# Measure.net
KiCad netlist of a schematic drawn in Altium Designer
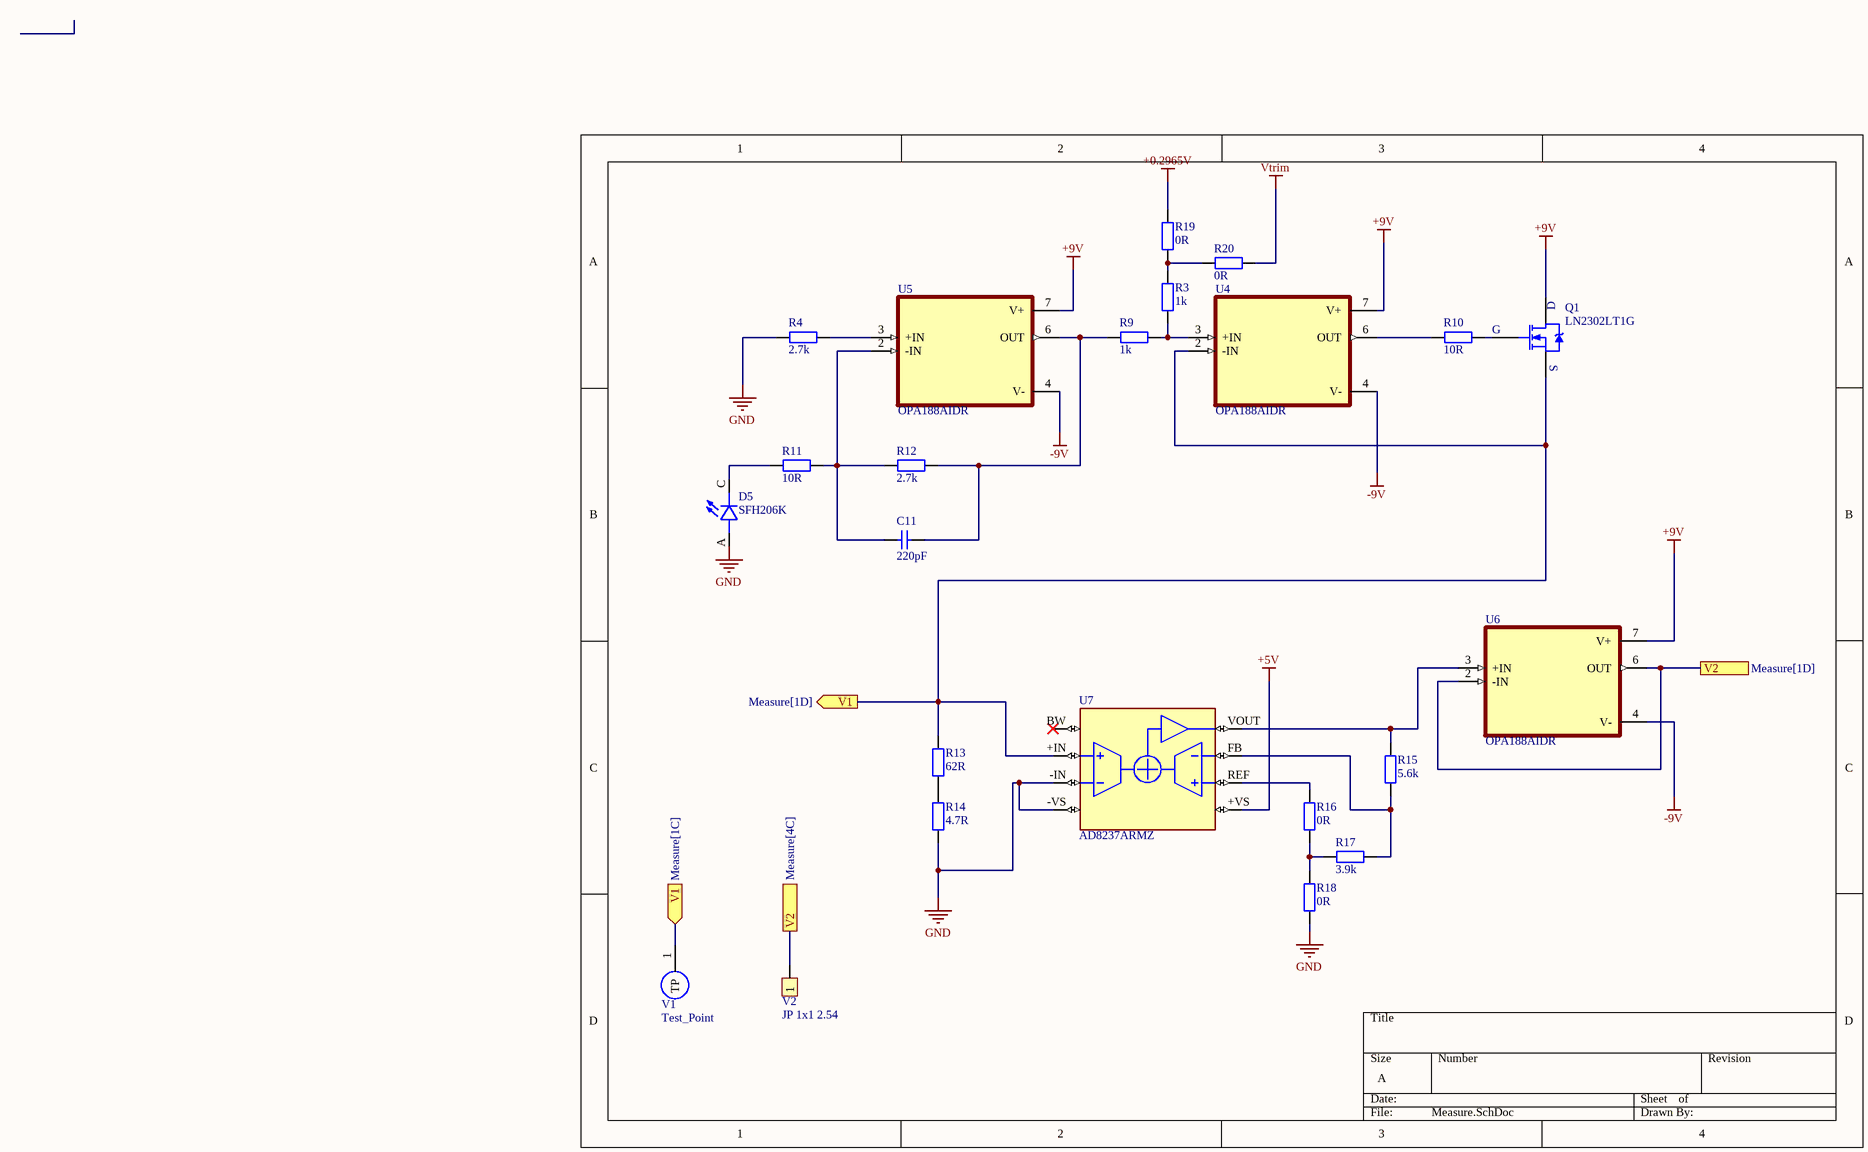
[diagram p0: Measure.SchDoc]

(export (version "E")
  (design (tool "Eeschema 10.0.6"))
  (components
    (comp (ref "C11")
      (value "220pF")
      (footprint "Tu 0603")
      (description "Dán")
      (libsource (lib "Tu dien") (part "Tu 0603 220pF 50V 10%"))
    )
    (comp (ref "D5")
      (value "SFH206K")
      (footprint "SFH206K")
      (description "photodiode, 850nm")
      (fields (field (name "MP") "L08R5000Q1") (field (name "MF") "LED Technology"))
      (libsource (lib "SFH206K") (part "SFH206K"))
    )
    (comp (ref "Q1")
      (value "LN2302LT1G")
      (footprint "SOT95P240X120-3N")
      (description "SOT-23-3, MOSFET kênh N, 20V, 2.3A")
      (libsource (lib "TranFet") (part "MOSFET"))
    )
    (comp (ref "R3")
      (value "1k")
      (footprint "tro smd 0603")
      (description "Dán")
      (libsource (lib "Dien Tro") (part "Tro 0603 1% 1k"))
    )
    (comp (ref "R4")
      (value "2.7k")
      (footprint "TRO SMD 0603")
      (description "dán")
      (libsource (lib "Dien Tro") (part "tro 0603 5% 2.7k"))
    )
    (comp (ref "R9")
      (value "1k")
      (footprint "tro smd 0603")
      (description "Dán")
      (libsource (lib "Dien Tro") (part "Tro 0603 1% 1k"))
    )
    (comp (ref "R10")
      (value "10R")
      (footprint "Tro smd 0603")
      (description "Dán")
      (libsource (lib "Dien Tro") (part "Tro 0603 5% 10R"))
    )
    (comp (ref "R11")
      (value "10R")
      (footprint "Tro smd 0603")
      (description "Dán")
      (libsource (lib "Dien Tro") (part "Tro 0603 5% 10R"))
    )
    (comp (ref "R12")
      (value "2.7k")
      (footprint "TRO SMD 0603")
      (description "dán")
      (libsource (lib "Dien Tro") (part "tro 0603 5% 2.7k"))
    )
    (comp (ref "R13")
      (value "62R")
      (footprint "TRO SMD 0603")
      (description "Dán")
      (libsource (lib "Dien Tro") (part "Tro 0603 1% 62R"))
    )
    (comp (ref "R14")
      (value "4.7R")
      (footprint "TRO SMD 0603")
      (description "Dán")
      (libsource (lib "Dien Tro") (part "Tro 0603 1% 4.7R"))
    )
    (comp (ref "R15")
      (value "5.6k")
      (footprint "TRO SMD 0603")
      (description "Dán")
      (libsource (lib "Dien Tro") (part "Tro 0603 1% 5.6k"))
    )
    (comp (ref "R16")
      (value "0R")
      (footprint "tro smd 0603")
      (description "Dán")
      (libsource (lib "Dien Tro") (part "Tro 0603 1% 0R"))
    )
    (comp (ref "R17")
      (value "3.9k")
      (footprint "TRO SMD 0603")
      (description "Dán")
      (libsource (lib "Dien Tro") (part "Tro 0805 1% 3.9k"))
    )
    (comp (ref "R18")
      (value "0R")
      (footprint "tro smd 0603")
      (description "Dán")
      (libsource (lib "Dien Tro") (part "Tro 0603 1% 0R"))
    )
    (comp (ref "R19")
      (value "0R")
      (footprint "tro smd 0603")
      (description "Dán")
      (libsource (lib "Dien Tro") (part "Tro 0603 1% 0R"))
    )
    (comp (ref "R20")
      (value "0R")
      (footprint "tro smd 0603")
      (description "Dán")
      (libsource (lib "Dien Tro") (part "Tro 0603 1% 0R"))
    )
    (comp (ref "U4")
      (value "OPA188AIDR")
      (footprint "SOIC127P599X175-8N")
      (description "Precision, Low-Noise, Rail-to-Rail Output, 36V Zero-Drift Operational Amplifier 8-SOIC -40 to 125")
      (fields (field (name "MF") "Texas Instruments") (field (name "DIGI-KEY_PART_NUMBER") "296-41346-1-ND"))
      (libsource (lib "OPA188AIDR") (part "OPA188AIDR"))
    )
    (comp (ref "U5")
      (value "OPA188AIDR")
      (footprint "SOIC127P599X175-8N")
      (description "Precision, Low-Noise, Rail-to-Rail Output, 36V Zero-Drift Operational Amplifier 8-SOIC -40 to 125")
      (fields (field (name "MF") "Texas Instruments") (field (name "DIGI-KEY_PART_NUMBER") "296-41346-1-ND"))
      (libsource (lib "OPA188AIDR") (part "OPA188AIDR"))
    )
    (comp (ref "U6")
      (value "OPA188AIDR")
      (footprint "SOIC127P599X175-8N")
      (description "Precision, Low-Noise, Rail-to-Rail Output, 36V Zero-Drift Operational Amplifier 8-SOIC -40 to 125")
      (fields (field (name "MF") "Texas Instruments") (field (name "DIGI-KEY_PART_NUMBER") "296-41346-1-ND"))
      (libsource (lib "OPA188AIDR") (part "OPA188AIDR"))
    )
    (comp (ref "U7")
      (value "AD8237ARMZ")
      (footprint "AD8237ARMZ")
      (description "Micropower, Zero Drift, True Rail-to-Rail Instrumentation Amplifier")
      (fields (field (name "MF") "Analog Devices"))
      (libsource (lib "AD8237ARMZ") (part "AD8237ARMZ"))
    )
    (comp (ref "V1")
      (value "Test_Point")
      (footprint "TP_2MM")
      (description "Test point, 2mm radius")
      (libsource (lib "SMIOT_Lib_Schematic") (part "Test_Point"))
    )
    (comp (ref "V2")
      (value "JP 1x1 2.54")
      (footprint "JP 1x1 DT")
      (description "Cắm")
      (libsource (lib "Jump") (part "JP 1x1 2.54 Duc Cong"))
    )
  )
  (nets
    (net (code "1") (name "+0.2965V") (class "Default")
      (node (ref "R19") (pin "2") (pinfunction "2_2") (pintype "passive"))
    )
    (net (code "2") (name "+5V") (class "Default")
      (node (ref "U7") (pin "+VS") (pinfunction "+VS_+VS") (pintype "bidirectional"))
    )
    (net (code "3") (name "+9V") (class "Default")
      (node (ref "Q1") (pin "3") (pinfunction "D_3") (pintype "passive"))
      (node (ref "U4") (pin "7") (pinfunction "V+_7") (pintype "power_in"))
      (node (ref "U5") (pin "7") (pinfunction "V+_7") (pintype "power_in"))
      (node (ref "U6") (pin "7") (pinfunction "V+_7") (pintype "power_in"))
    )
    (net (code "4") (name "-9V") (class "Default")
      (node (ref "U4") (pin "4") (pinfunction "V-_4") (pintype "power_in"))
      (node (ref "U5") (pin "4") (pinfunction "V-_4") (pintype "power_in"))
      (node (ref "U6") (pin "4") (pinfunction "V-_4") (pintype "power_in"))
    )
    (net (code "5") (name "/V1") (class "Default")
      (node (ref "Q1") (pin "2") (pinfunction "S_2") (pintype "passive"))
      (node (ref "R13") (pin "2") (pinfunction "2_2") (pintype "passive"))
      (node (ref "U4") (pin "2") (pinfunction "-IN_2") (pintype "input"))
      (node (ref "U7") (pin "+IN") (pinfunction "+IN_+IN") (pintype "bidirectional"))
      (node (ref "V1") (pin "1") (pinfunction "TP_1") (pintype "passive"))
    )
    (net (code "6") (name "/V2") (class "Default")
      (node (ref "U6") (pin "2") (pinfunction "-IN_2") (pintype "input"))
      (node (ref "U6") (pin "6") (pinfunction "OUT_6") (pintype "output"))
      (node (ref "V2") (pin "1") (pinfunction "1_1") (pintype "passive"))
    )
    (net (code "7") (name "GND") (class "Default")
      (node (ref "D5") (pin "A") (pinfunction "A_A") (pintype "passive"))
      (node (ref "R14") (pin "1") (pinfunction "1_1") (pintype "passive"))
      (node (ref "R18") (pin "2") (pinfunction "2_2") (pintype "passive"))
      (node (ref "R4") (pin "1") (pinfunction "1_1") (pintype "passive"))
      (node (ref "U7") (pin "-IN") (pinfunction "-IN_-IN") (pintype "bidirectional"))
      (node (ref "U7") (pin "-VS") (pinfunction "-VS_-VS") (pintype "bidirectional"))
    )
    (net (code "8") (name "Net-(D5-PadC)") (class "Default")
      (node (ref "D5") (pin "C") (pinfunction "C_C") (pintype "passive"))
      (node (ref "R11") (pin "1") (pinfunction "1_1") (pintype "passive"))
    )
    (net (code "9") (name "Net-(Q1-G)") (class "Default")
      (node (ref "Q1") (pin "1") (pinfunction "G_1") (pintype "passive"))
      (node (ref "R10") (pin "2") (pinfunction "2_2") (pintype "passive"))
    )
    (net (code "10") (name "Net-(R13-Pad1)") (class "Default")
      (node (ref "R13") (pin "1") (pinfunction "1_1") (pintype "passive"))
      (node (ref "R14") (pin "2") (pinfunction "2_2") (pintype "passive"))
    )
    (net (code "11") (name "Net-(R15-Pad1)") (class "Default")
      (node (ref "R15") (pin "1") (pinfunction "1_1") (pintype "passive"))
      (node (ref "R17") (pin "2") (pinfunction "2_2") (pintype "passive"))
      (node (ref "U7") (pin "FB") (pinfunction "FB_FB") (pintype "bidirectional"))
    )
    (net (code "12") (name "Net-(R16-Pad1)") (class "Default")
      (node (ref "R16") (pin "1") (pinfunction "1_1") (pintype "passive"))
      (node (ref "U7") (pin "REF") (pinfunction "REF_REF") (pintype "bidirectional"))
    )
    (net (code "13") (name "Net-(R16-Pad2)") (class "Default")
      (node (ref "R16") (pin "2") (pinfunction "2_2") (pintype "passive"))
      (node (ref "R17") (pin "1") (pinfunction "1_1") (pintype "passive"))
      (node (ref "R18") (pin "1") (pinfunction "1_1") (pintype "passive"))
    )
    (net (code "14") (name "Net-(R19-Pad1)") (class "Default")
      (node (ref "R19") (pin "1") (pinfunction "1_1") (pintype "passive"))
      (node (ref "R20") (pin "1") (pinfunction "1_1") (pintype "passive"))
      (node (ref "R3") (pin "2") (pinfunction "2_2") (pintype "passive"))
    )
    (net (code "15") (name "Net-(U4-+IN)") (class "Default")
      (node (ref "R3") (pin "1") (pinfunction "1_1") (pintype "passive"))
      (node (ref "R9") (pin "2") (pinfunction "2_2") (pintype "passive"))
      (node (ref "U4") (pin "3") (pinfunction "+IN_3") (pintype "input"))
    )
    (net (code "16") (name "Net-(U4-OUT)") (class "Default")
      (node (ref "R10") (pin "1") (pinfunction "1_1") (pintype "passive"))
      (node (ref "U4") (pin "6") (pinfunction "OUT_6") (pintype "output"))
    )
    (net (code "17") (name "Net-(U5-+IN)") (class "Default")
      (node (ref "R4") (pin "2") (pinfunction "2_2") (pintype "passive"))
      (node (ref "U5") (pin "3") (pinfunction "+IN_3") (pintype "input"))
    )
    (net (code "18") (name "Net-(U5--IN)") (class "Default")
      (node (ref "C11") (pin "2") (pinfunction "2_2") (pintype "passive"))
      (node (ref "R11") (pin "2") (pinfunction "2_2") (pintype "passive"))
      (node (ref "R12") (pin "1") (pinfunction "1_1") (pintype "passive"))
      (node (ref "U5") (pin "2") (pinfunction "-IN_2") (pintype "input"))
    )
    (net (code "19") (name "Net-(U5-OUT)") (class "Default")
      (node (ref "C11") (pin "1") (pinfunction "1_1") (pintype "passive"))
      (node (ref "R12") (pin "2") (pinfunction "2_2") (pintype "passive"))
      (node (ref "R9") (pin "1") (pinfunction "1_1") (pintype "passive"))
      (node (ref "U5") (pin "6") (pinfunction "OUT_6") (pintype "output"))
    )
    (net (code "20") (name "Net-(U6-+IN)") (class "Default")
      (node (ref "R15") (pin "2") (pinfunction "2_2") (pintype "passive"))
      (node (ref "U6") (pin "3") (pinfunction "+IN_3") (pintype "input"))
      (node (ref "U7") (pin "VOUT") (pinfunction "VOUT_VOUT") (pintype "bidirectional"))
    )
    (net (code "21") (name "Vtrim") (class "Default")
      (node (ref "R20") (pin "2") (pinfunction "2_2") (pintype "passive"))
    )
    (net (code "22") (name "unconnected-(U7-PadBW)") (class "Default")
      (node (ref "U7") (pin "BW") (pinfunction "BW_BW") (pintype "bidirectional+no_connect"))
    )
  )
)
